# Encoders.net
KiCad netlist of a schematic drawn in Altium Designer
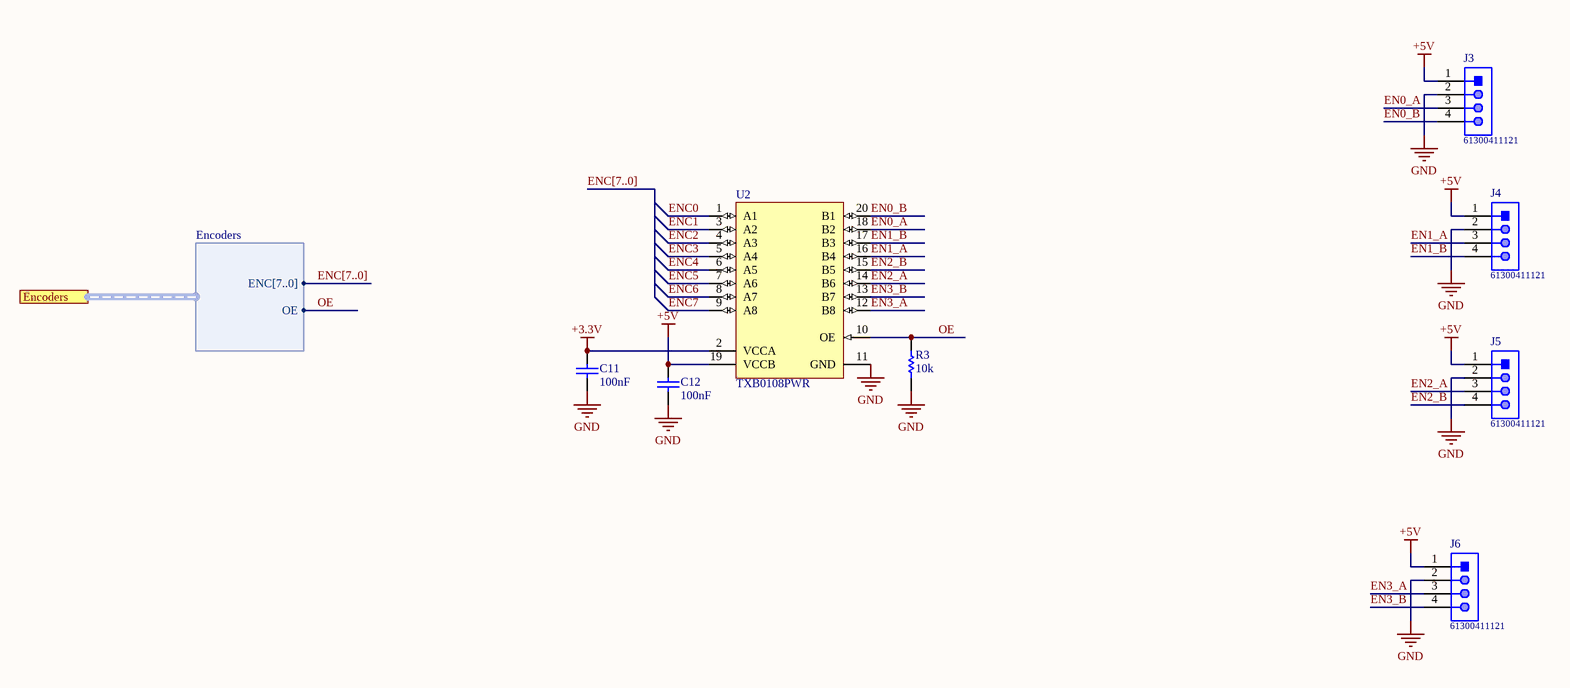
[diagram p0: Encoders.SchDoc]

(export (version "E")
  (design (tool "Eeschema 10.0.6"))
  (components
    (comp (ref "C11")
      (value "100nF")
      (footprint "0402")
      (description "TDK - C1005X7R1C104K050BC. - CERAMIC CAPACITOR, 0.1UF, 16V, X7R, 10%, 0402, FULL REEL")
      (fields
        (field (name "MANUFACTURER") "TDK")
        (field (name "MANUFACTURER PART NUMBER") "C1005X7R1C104K050BC")
      )
      (libsource (lib "altium-library") (part "Capacitor"))
    )
    (comp (ref "C12")
      (value "100nF")
      (footprint "0402")
      (description "TDK - C1005X7R1C104K050BC. - CERAMIC CAPACITOR, 0.1UF, 16V, X7R, 10%, 0402, FULL REEL")
      (fields
        (field (name "MANUFACTURER") "TDK")
        (field (name "MANUFACTURER PART NUMBER") "C1005X7R1C104K050BC")
      )
      (libsource (lib "altium-library") (part "Capacitor"))
    )
    (comp (ref "J3")
      (value "61300411121")
      (footprint "61300411121")
      (description "THT Vertical Pin Header WR-PHD, Pitch 2.54 mm, Single Row, 4 pins")
      (fields (field (name "MANUFACTURER") "Wurth Elektronik") (field (name "PUBLISHER") "WurthElektronik"))
      (libsource (lib "Altium Content Vault") (part "WE-CN-1P-M-R4"))
    )
    (comp (ref "J4")
      (value "61300411121")
      (footprint "61300411121")
      (description "THT Vertical Pin Header WR-PHD, Pitch 2.54 mm, Single Row, 4 pins")
      (fields (field (name "MANUFACTURER") "Wurth Elektronik") (field (name "PUBLISHER") "WurthElektronik"))
      (libsource (lib "Altium Content Vault") (part "WE-CN-1P-M-R4"))
    )
    (comp (ref "J5")
      (value "61300411121")
      (footprint "61300411121")
      (description "THT Vertical Pin Header WR-PHD, Pitch 2.54 mm, Single Row, 4 pins")
      (fields (field (name "MANUFACTURER") "Wurth Elektronik") (field (name "PUBLISHER") "WurthElektronik"))
      (libsource (lib "Altium Content Vault") (part "WE-CN-1P-M-R4"))
    )
    (comp (ref "J6")
      (value "61300411121")
      (footprint "61300411121")
      (description "THT Vertical Pin Header WR-PHD, Pitch 2.54 mm, Single Row, 4 pins")
      (fields (field (name "MANUFACTURER") "Wurth Elektronik") (field (name "PUBLISHER") "WurthElektronik"))
      (libsource (lib "Altium Content Vault") (part "WE-CN-1P-M-R4"))
    )
    (comp (ref "R3")
      (value "10k")
      (footprint "0402")
      (description "D10/CRCW0402-C 100 10K 1% ET7")
      (fields
        (field (name "MANUFACTURER") "Vishay")
        (field (name "MANUFACTURER PART NUMBER") "CRCW040210K0FKEDC")
      )
      (libsource (lib "altium-library") (part "Resistor"))
    )
    (comp (ref "U2")
      (value "TXB0108PWR")
      (footprint "PW0020A_L")
      (fields (field (name "MANUFACTURER") "Texas Instruments"))
      (libsource (lib "Altium Content Vault") (part "TI-TXB0108-PW-20"))
    )
  )
  (nets
    (net (code "2") (name "+3.3V") (class "Default")
      (node (ref "C11") (pin "2") (pinfunction "2_2") (pintype "passive"))
      (node (ref "U2") (pin "2") (pinfunction "VCCA_2") (pintype "power_in"))
    )
    (net (code "3") (name "+5V") (class "Default")
      (node (ref "C12") (pin "2") (pinfunction "2_2") (pintype "passive"))
      (node (ref "J3") (pin "1") (pinfunction "1_1") (pintype "passive"))
      (node (ref "J4") (pin "1") (pinfunction "1_1") (pintype "passive"))
      (node (ref "J5") (pin "1") (pinfunction "1_1") (pintype "passive"))
      (node (ref "J6") (pin "1") (pinfunction "1_1") (pintype "passive"))
      (node (ref "U2") (pin "19") (pinfunction "VCCB_19") (pintype "power_in"))
    )
    (net (code "4") (name "/EN0_A") (class "Default")
      (node (ref "J3") (pin "3") (pinfunction "3_3") (pintype "passive"))
      (node (ref "U2") (pin "18") (pinfunction "B2_18") (pintype "bidirectional"))
    )
    (net (code "5") (name "/EN0_B") (class "Default")
      (node (ref "J3") (pin "4") (pinfunction "4_4") (pintype "passive"))
      (node (ref "U2") (pin "20") (pinfunction "B1_20") (pintype "bidirectional"))
    )
    (net (code "6") (name "/EN1_A") (class "Default")
      (node (ref "J4") (pin "3") (pinfunction "3_3") (pintype "passive"))
      (node (ref "U2") (pin "16") (pinfunction "B4_16") (pintype "bidirectional"))
    )
    (net (code "7") (name "/EN1_B") (class "Default")
      (node (ref "J4") (pin "4") (pinfunction "4_4") (pintype "passive"))
      (node (ref "U2") (pin "17") (pinfunction "B3_17") (pintype "bidirectional"))
    )
    (net (code "8") (name "/EN2_A") (class "Default")
      (node (ref "J5") (pin "3") (pinfunction "3_3") (pintype "passive"))
      (node (ref "U2") (pin "14") (pinfunction "B6_14") (pintype "bidirectional"))
    )
    (net (code "9") (name "/EN2_B") (class "Default")
      (node (ref "J5") (pin "4") (pinfunction "4_4") (pintype "passive"))
      (node (ref "U2") (pin "15") (pinfunction "B5_15") (pintype "bidirectional"))
    )
    (net (code "10") (name "/EN3_A") (class "Default")
      (node (ref "J6") (pin "3") (pinfunction "3_3") (pintype "passive"))
      (node (ref "U2") (pin "12") (pinfunction "B8_12") (pintype "bidirectional"))
    )
    (net (code "11") (name "/EN3_B") (class "Default")
      (node (ref "J6") (pin "4") (pinfunction "4_4") (pintype "passive"))
      (node (ref "U2") (pin "13") (pinfunction "B7_13") (pintype "bidirectional"))
    )
    (net (code "12") (name "/ENC0") (class "Default")
      (node (ref "U2") (pin "1") (pinfunction "A1_1") (pintype "bidirectional"))
    )
    (net (code "13") (name "/ENC1") (class "Default")
      (node (ref "U2") (pin "3") (pinfunction "A2_3") (pintype "bidirectional"))
    )
    (net (code "14") (name "/ENC2") (class "Default")
      (node (ref "U2") (pin "4") (pinfunction "A3_4") (pintype "bidirectional"))
    )
    (net (code "15") (name "/ENC3") (class "Default")
      (node (ref "U2") (pin "5") (pinfunction "A4_5") (pintype "bidirectional"))
    )
    (net (code "16") (name "/ENC4") (class "Default")
      (node (ref "U2") (pin "6") (pinfunction "A5_6") (pintype "bidirectional"))
    )
    (net (code "17") (name "/ENC5") (class "Default")
      (node (ref "U2") (pin "7") (pinfunction "A6_7") (pintype "bidirectional"))
    )
    (net (code "18") (name "/ENC6") (class "Default")
      (node (ref "U2") (pin "8") (pinfunction "A7_8") (pintype "bidirectional"))
    )
    (net (code "19") (name "/ENC7") (class "Default")
      (node (ref "U2") (pin "9") (pinfunction "A8_9") (pintype "bidirectional"))
    )
    (net (code "21") (name "/OE") (class "Default")
      (node (ref "R3") (pin "2") (pinfunction "2_2") (pintype "passive"))
      (node (ref "U2") (pin "10") (pinfunction "OE_10") (pintype "input"))
    )
    (net (code "23") (name "GND") (class "Default")
      (node (ref "C11") (pin "1") (pinfunction "1_1") (pintype "passive"))
      (node (ref "C12") (pin "1") (pinfunction "1_1") (pintype "passive"))
      (node (ref "J3") (pin "2") (pinfunction "2_2") (pintype "passive"))
      (node (ref "J4") (pin "2") (pinfunction "2_2") (pintype "passive"))
      (node (ref "J5") (pin "2") (pinfunction "2_2") (pintype "passive"))
      (node (ref "J6") (pin "2") (pinfunction "2_2") (pintype "passive"))
      (node (ref "R3") (pin "1") (pinfunction "1_1") (pintype "passive"))
      (node (ref "U2") (pin "11") (pinfunction "GND_11") (pintype "power_in"))
    )
  )
)
